# 03_Mechanicals.net
KiCad netlist of a schematic drawn in Altium Designer
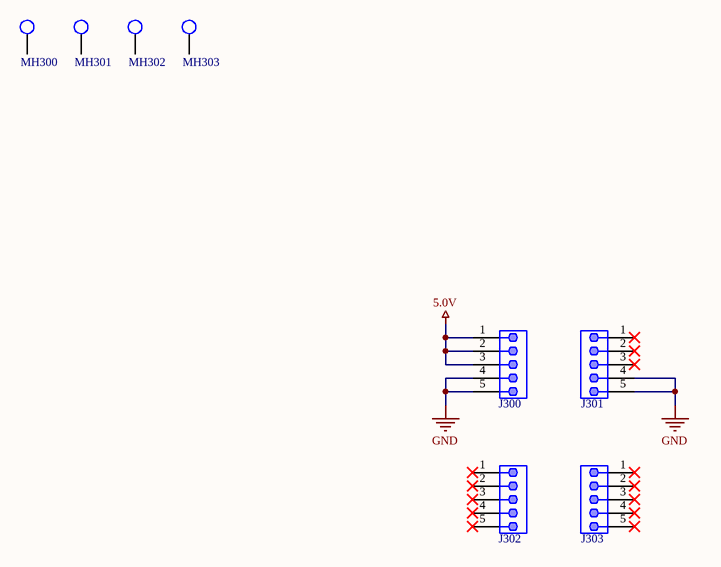
[diagram p0: 03_Mechanicals.SchDoc]

(export (version "E")
  (design (tool "Eeschema 10.0.6"))
  (components
    (comp (ref "J300")
      (value "CONN_HEADER_MALE_1x5")
      (footprint "HDR1X5")
      (description "Header, 5-Pin")
      (libsource (lib "Connectors") (part "CONN_HEADER_MALE_1x5"))
    )
    (comp (ref "J301")
      (value "CONN_HEADER_MALE_1x5")
      (footprint "HDR1X5")
      (description "Header, 5-Pin")
      (libsource (lib "") (part "CONN_HEADER_MALE_1x5_1"))
    )
    (comp (ref "J302")
      (value "CONN_HEADER_MALE_1x5")
      (footprint "HDR1X5")
      (description "Header, 5-Pin")
      (libsource (lib "Connectors") (part "CONN_HEADER_MALE_1x5"))
    )
    (comp (ref "J303")
      (value "CONN_HEADER_MALE_1x5")
      (footprint "HDR1X5")
      (description "Header, 5-Pin")
      (libsource (lib "") (part "CONN_HEADER_MALE_1x5_1"))
    )
    (comp (ref "MH300")
      (value "MHOLE_2_55MM")
      (footprint "MHOLE_2_55MM")
      (description "Mounting Holde")
      (fields (field (name "MANUFACTURER PART NUMBER") "UW MTHOLE"))
      (libsource (lib "ece315-2018-fall") (part "MHOLE_2_55MM"))
    )
    (comp (ref "MH301")
      (value "MHOLE_2_55MM")
      (footprint "MHOLE_2_55MM")
      (description "Mounting Holde")
      (fields (field (name "MANUFACTURER PART NUMBER") "UW MTHOLE"))
      (libsource (lib "ece315-2018-fall") (part "MHOLE_2_55MM"))
    )
    (comp (ref "MH302")
      (value "MHOLE_2_55MM")
      (footprint "MHOLE_2_55MM")
      (description "Mounting Holde")
      (fields (field (name "MANUFACTURER PART NUMBER") "UW MTHOLE"))
      (libsource (lib "ece315-2018-fall") (part "MHOLE_2_55MM"))
    )
    (comp (ref "MH303")
      (value "MHOLE_2_55MM")
      (footprint "MHOLE_2_55MM")
      (description "Mounting Holde")
      (fields (field (name "MANUFACTURER PART NUMBER") "UW MTHOLE"))
      (libsource (lib "ece315-2018-fall") (part "MHOLE_2_55MM"))
    )
  )
  (nets
    (net (code "1") (name "5.0V") (class "Default")
      (node (ref "J300") (pin "1") (pinfunction "1_1") (pintype "passive"))
      (node (ref "J300") (pin "2") (pinfunction "2_2") (pintype "passive"))
      (node (ref "J300") (pin "3") (pinfunction "3_3") (pintype "passive"))
    )
    (net (code "2") (name "GND") (class "Default")
      (node (ref "J300") (pin "4") (pinfunction "4_4") (pintype "passive"))
      (node (ref "J300") (pin "5") (pinfunction "5_5") (pintype "passive"))
      (node (ref "J301") (pin "4") (pinfunction "4_4") (pintype "passive"))
      (node (ref "J301") (pin "5") (pinfunction "5_5") (pintype "passive"))
    )
    (net (code "3") (name "unconnected-(J301-Pad1)") (class "Default")
      (node (ref "J301") (pin "1") (pinfunction "1_1") (pintype "passive+no_connect"))
    )
    (net (code "4") (name "unconnected-(J301-Pad2)") (class "Default")
      (node (ref "J301") (pin "2") (pinfunction "2_2") (pintype "passive+no_connect"))
    )
    (net (code "5") (name "unconnected-(J301-Pad3)") (class "Default")
      (node (ref "J301") (pin "3") (pinfunction "3_3") (pintype "passive+no_connect"))
    )
    (net (code "6") (name "unconnected-(J302-Pad1)") (class "Default")
      (node (ref "J302") (pin "1") (pinfunction "1_1") (pintype "passive+no_connect"))
    )
    (net (code "7") (name "unconnected-(J302-Pad2)") (class "Default")
      (node (ref "J302") (pin "2") (pinfunction "2_2") (pintype "passive+no_connect"))
    )
    (net (code "8") (name "unconnected-(J302-Pad3)") (class "Default")
      (node (ref "J302") (pin "3") (pinfunction "3_3") (pintype "passive+no_connect"))
    )
    (net (code "9") (name "unconnected-(J302-Pad4)") (class "Default")
      (node (ref "J302") (pin "4") (pinfunction "4_4") (pintype "passive+no_connect"))
    )
    (net (code "10") (name "unconnected-(J302-Pad5)") (class "Default")
      (node (ref "J302") (pin "5") (pinfunction "5_5") (pintype "passive+no_connect"))
    )
    (net (code "11") (name "unconnected-(J303-Pad1)") (class "Default")
      (node (ref "J303") (pin "1") (pinfunction "1_1") (pintype "passive+no_connect"))
    )
    (net (code "12") (name "unconnected-(J303-Pad2)") (class "Default")
      (node (ref "J303") (pin "2") (pinfunction "2_2") (pintype "passive+no_connect"))
    )
    (net (code "13") (name "unconnected-(J303-Pad3)") (class "Default")
      (node (ref "J303") (pin "3") (pinfunction "3_3") (pintype "passive+no_connect"))
    )
    (net (code "14") (name "unconnected-(J303-Pad4)") (class "Default")
      (node (ref "J303") (pin "4") (pinfunction "4_4") (pintype "passive+no_connect"))
    )
    (net (code "15") (name "unconnected-(J303-Pad5)") (class "Default")
      (node (ref "J303") (pin "5") (pinfunction "5_5") (pintype "passive+no_connect"))
    )
    (net (code "16") (name "unconnected-(MH300-Pad1)") (class "Default")
      (node (ref "MH300") (pin "1") (pintype "passive"))
    )
    (net (code "17") (name "unconnected-(MH301-Pad1)") (class "Default")
      (node (ref "MH301") (pin "1") (pintype "passive"))
    )
    (net (code "18") (name "unconnected-(MH302-Pad1)") (class "Default")
      (node (ref "MH302") (pin "1") (pintype "passive"))
    )
    (net (code "19") (name "unconnected-(MH303-Pad1)") (class "Default")
      (node (ref "MH303") (pin "1") (pintype "passive"))
    )
  )
)
